# Agilent_3Ghz_option.net
KiCad netlist of a schematic drawn in Altium Designer
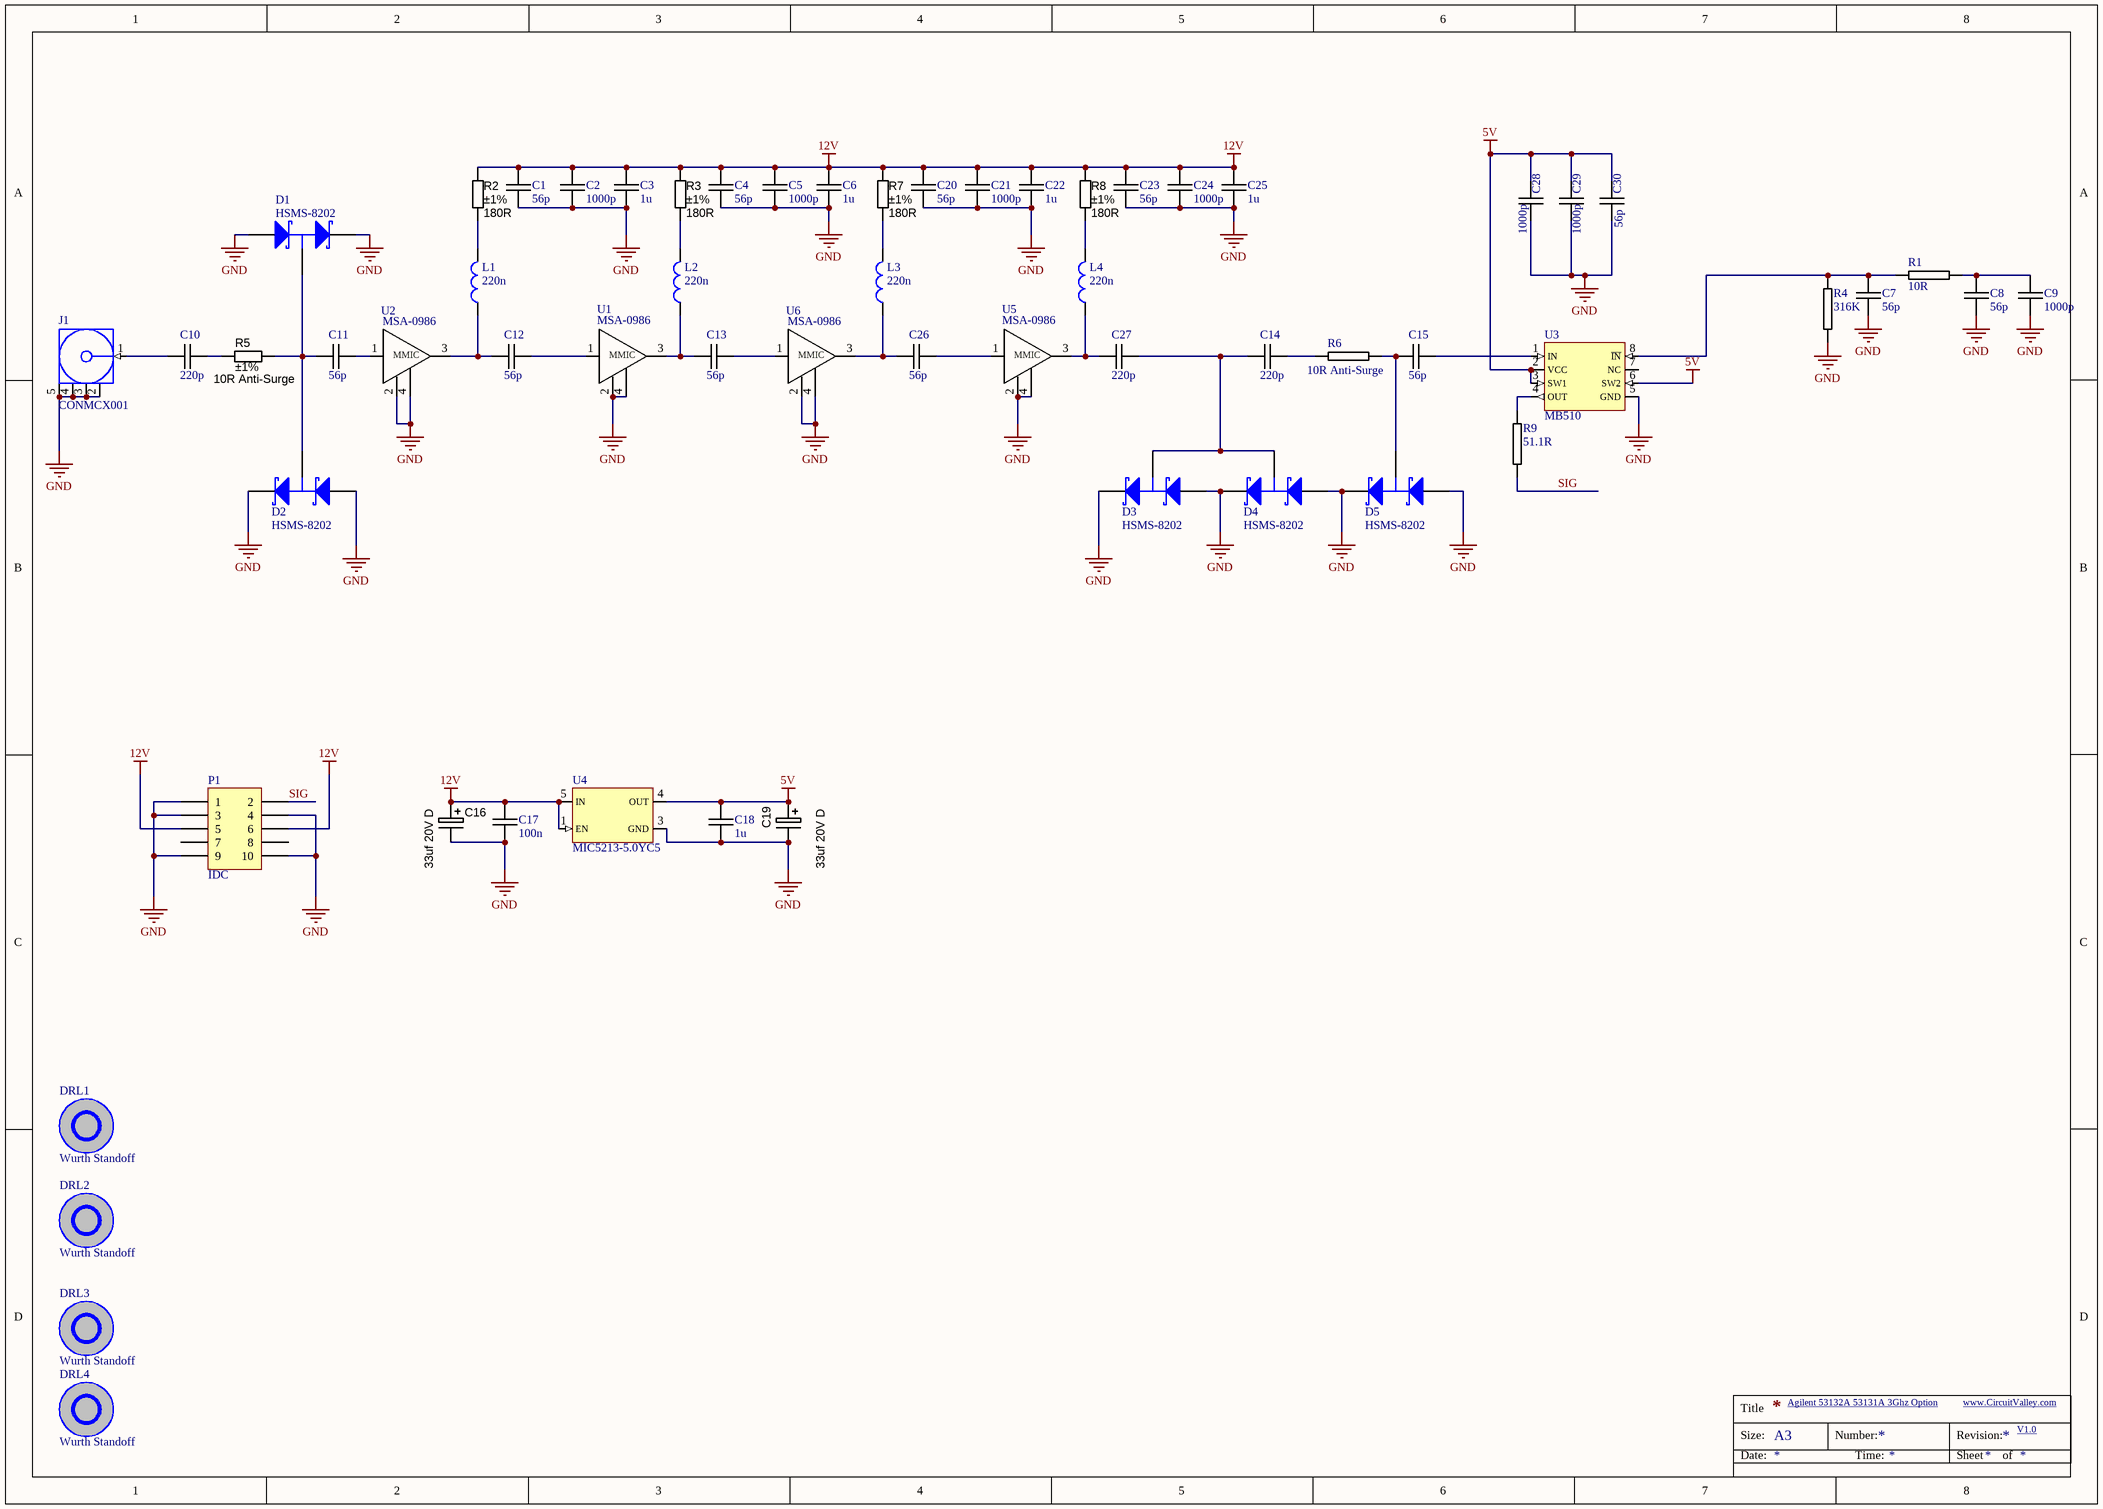
[diagram p0: Agilent_3Ghz_option.SchDoc]

(export (version "E")
  (design (tool "Eeschema 10.0.6"))
  (components
    (comp (ref "C1")
      (value "56p")
      (footprint "0805C-TBD")
      (description "CAPACITOR 0805 CERAMIC VALUE TO BE DETERMINED")
      (fields (field (name "PART") "CC0805FRNPO9BN560"))
      (libsource (lib "Generic") (part "0805C-TBD"))
    )
    (comp (ref "C2")
      (value "1000p")
      (footprint "0805C-TBD")
      (description "CAPACITOR 0805 CERAMIC VALUE TO BE DETERMINED")
      (fields (field (name "PART") "GRM2165C1H102FA01J"))
      (libsource (lib "Generic") (part "0805C-TBD"))
    )
    (comp (ref "C3")
      (value "1u")
      (footprint "0805C-TBD")
      (description "CAPACITOR 0805 CERAMIC VALUE TO BE DETERMINED")
      (fields (field (name "PART") "VJ0805V105ZXJCW1BC"))
      (libsource (lib "Generic") (part "0805C-TBD"))
    )
    (comp (ref "C4")
      (value "56p")
      (footprint "0805C-TBD")
      (description "CAPACITOR 0805 CERAMIC VALUE TO BE DETERMINED")
      (fields (field (name "PART") "CC0805FRNPO9BN560"))
      (libsource (lib "Generic") (part "0805C-TBD"))
    )
    (comp (ref "C5")
      (value "1000p")
      (footprint "0805C-TBD")
      (description "CAPACITOR 0805 CERAMIC VALUE TO BE DETERMINED")
      (fields (field (name "PART") "GRM2165C1H102FA01J"))
      (libsource (lib "Generic") (part "0805C-TBD"))
    )
    (comp (ref "C6")
      (value "1u")
      (footprint "0805C-TBD")
      (description "CAPACITOR 0805 CERAMIC VALUE TO BE DETERMINED")
      (fields (field (name "PART") "VJ0805V105ZXJCW1BC"))
      (libsource (lib "Generic") (part "0805C-TBD"))
    )
    (comp (ref "C7")
      (value "56p")
      (footprint "0805C-TBD")
      (description "CAPACITOR 0805 CERAMIC VALUE TO BE DETERMINED")
      (fields (field (name "PART") "CC0805FRNPO9BN560"))
      (libsource (lib "Generic") (part "0805C-TBD"))
    )
    (comp (ref "C8")
      (value "56p")
      (footprint "0805C-TBD")
      (description "CAPACITOR 0805 CERAMIC VALUE TO BE DETERMINED")
      (fields (field (name "PART") "CC0805FRNPO9BN560"))
      (libsource (lib "Generic") (part "0805C-TBD"))
    )
    (comp (ref "C9")
      (value "1000p")
      (footprint "0805C-TBD")
      (description "CAPACITOR 0805 CERAMIC VALUE TO BE DETERMINED")
      (fields (field (name "PART") "GRM2165C1H102FA01J"))
      (libsource (lib "Generic") (part "0805C-TBD"))
    )
    (comp (ref "C10")
      (value "220p")
      (footprint "0805C-TBD")
      (description "CAPACITOR 0805 CERAMIC VALUE TO BE DETERMINED")
      (fields (field (name "PART") "CC0805FRNPO9BN221"))
      (libsource (lib "Generic") (part "0805C-TBD"))
    )
    (comp (ref "C11")
      (value "56p")
      (footprint "0805C-TBD")
      (description "CAPACITOR 0805 CERAMIC VALUE TO BE DETERMINED")
      (fields (field (name "PART") "CC0805FRNPO9BN560"))
      (libsource (lib "Generic") (part "0805C-TBD"))
    )
    (comp (ref "C12")
      (value "56p")
      (footprint "0805C-TBD")
      (description "CAPACITOR 0805 CERAMIC VALUE TO BE DETERMINED")
      (fields (field (name "PART") "CC0805FRNPO9BN560"))
      (libsource (lib "Generic") (part "0805C-TBD"))
    )
    (comp (ref "C13")
      (value "56p")
      (footprint "0805C-TBD")
      (description "CAPACITOR 0805 CERAMIC VALUE TO BE DETERMINED")
      (fields (field (name "PART") "CC0805FRNPO9BN560"))
      (libsource (lib "Generic") (part "0805C-TBD"))
    )
    (comp (ref "C14")
      (value "220p")
      (footprint "0805C-TBD")
      (description "CAPACITOR 0805 CERAMIC VALUE TO BE DETERMINED")
      (fields (field (name "PART") "CC0805FRNPO9BN221"))
      (libsource (lib "Generic") (part "0805C-TBD"))
    )
    (comp (ref "C15")
      (value "56p")
      (footprint "0805C-TBD")
      (description "CAPACITOR 0805 CERAMIC VALUE TO BE DETERMINED")
      (fields (field (name "PART") "CC0805FRNPO9BN560"))
      (libsource (lib "Generic") (part "0805C-TBD"))
    )
    (comp (ref "C16")
      (value "33uf 20V D")
      (footprint "CAPMP7343X310N")
      (description "Capacitor SMD Tant 330uF 20% 6V3 2917")
      (fields
        (field (name "TOLERANCE") "±20%")
        (field (name "MANUFACTURER PART NUMBER") "T520D337M006ATE015")
      )
      (libsource (lib "PBL - Capacitors") (part "CAPT_330u_2917_6V3"))
    )
    (comp (ref "C17")
      (value "100n")
      (footprint "0805C-TBD")
      (description "CAPACITOR 0805 CERAMIC VALUE TO BE DETERMINED")
      (fields (field (name "PART") "GRM21BR71H104KA01K"))
      (libsource (lib "Generic") (part "0805C-TBD"))
    )
    (comp (ref "C18")
      (value "1u")
      (footprint "0805C-TBD")
      (description "CAPACITOR 0805 CERAMIC VALUE TO BE DETERMINED")
      (fields (field (name "PART") "VJ0805V105ZXJCW1BC"))
      (libsource (lib "Generic") (part "0805C-TBD"))
    )
    (comp (ref "C19")
      (value "33uf 20V D")
      (footprint "CAPMP7343X310N")
      (description "Capacitor SMD Tant 330uF 20% 6V3 2917")
      (fields
        (field (name "TOLERANCE") "±20%")
        (field (name "MANUFACTURER PART NUMBER") "T520D337M006ATE015")
      )
      (libsource (lib "PBL - Capacitors") (part "CAPT_330u_2917_6V3"))
    )
    (comp (ref "C20")
      (value "56p")
      (footprint "0805C-TBD")
      (description "CAPACITOR 0805 CERAMIC VALUE TO BE DETERMINED")
      (fields (field (name "PART") "CC0805FRNPO9BN560"))
      (libsource (lib "Generic") (part "0805C-TBD"))
    )
    (comp (ref "C21")
      (value "1000p")
      (footprint "0805C-TBD")
      (description "CAPACITOR 0805 CERAMIC VALUE TO BE DETERMINED")
      (fields (field (name "PART") "GRM2165C1H102FA01J"))
      (libsource (lib "Generic") (part "0805C-TBD"))
    )
    (comp (ref "C22")
      (value "1u")
      (footprint "0805C-TBD")
      (description "CAPACITOR 0805 CERAMIC VALUE TO BE DETERMINED")
      (fields (field (name "PART") "VJ0805V105ZXJCW1BC"))
      (libsource (lib "Generic") (part "0805C-TBD"))
    )
    (comp (ref "C23")
      (value "56p")
      (footprint "0805C-TBD")
      (description "CAPACITOR 0805 CERAMIC VALUE TO BE DETERMINED")
      (fields (field (name "PART") "CC0805FRNPO9BN560"))
      (libsource (lib "Generic") (part "0805C-TBD"))
    )
    (comp (ref "C24")
      (value "1000p")
      (footprint "0805C-TBD")
      (description "CAPACITOR 0805 CERAMIC VALUE TO BE DETERMINED")
      (fields (field (name "PART") "GRM2165C1H102FA01J"))
      (libsource (lib "Generic") (part "0805C-TBD"))
    )
    (comp (ref "C25")
      (value "1u")
      (footprint "0805C-TBD")
      (description "CAPACITOR 0805 CERAMIC VALUE TO BE DETERMINED")
      (fields (field (name "PART") "VJ0805V105ZXJCW1BC"))
      (libsource (lib "Generic") (part "0805C-TBD"))
    )
    (comp (ref "C26")
      (value "56p")
      (footprint "0805C-TBD")
      (description "CAPACITOR 0805 CERAMIC VALUE TO BE DETERMINED")
      (fields (field (name "PART") "CC0805FRNPO9BN560"))
      (libsource (lib "Generic") (part "0805C-TBD"))
    )
    (comp (ref "C27")
      (value "220p")
      (footprint "0805C-TBD")
      (description "CAPACITOR 0805 CERAMIC VALUE TO BE DETERMINED")
      (fields (field (name "PART") "CC0805FRNPO9BN221"))
      (libsource (lib "Generic") (part "0805C-TBD"))
    )
    (comp (ref "C28")
      (value "1000p")
      (footprint "0805C-TBD")
      (description "CAPACITOR 0805 CERAMIC VALUE TO BE DETERMINED")
      (fields (field (name "PART") "GRM2165C1H102FA01J"))
      (libsource (lib "Generic") (part "0805C-TBD"))
    )
    (comp (ref "C29")
      (value "1000p")
      (footprint "0805C-TBD")
      (description "CAPACITOR 0805 CERAMIC VALUE TO BE DETERMINED")
      (fields (field (name "PART") "GRM2165C1H102FA01J"))
      (libsource (lib "Generic") (part "0805C-TBD"))
    )
    (comp (ref "C30")
      (value "56p")
      (footprint "0805C-TBD")
      (description "CAPACITOR 0805 CERAMIC VALUE TO BE DETERMINED")
      (fields (field (name "PART") "CC0805FRNPO9BN560"))
      (libsource (lib "Generic") (part "0805C-TBD"))
    )
    (comp (ref "D1")
      (value "HSMS-8202")
      (footprint "SOT23_N")
      (description "Schottky Barrier Double Diode")
      (fields (field (name "PUBLISHER") "Altium Limited"))
      (libsource (lib "Philips Discrete Diode - Schottky") (part "BAT54S"))
    )
    (comp (ref "D2")
      (value "HSMS-8202")
      (footprint "SOT23_N")
      (description "Schottky Barrier Double Diode")
      (fields (field (name "PUBLISHER") "Altium Limited"))
      (libsource (lib "Philips Discrete Diode - Schottky") (part "BAT54S"))
    )
    (comp (ref "D3")
      (value "HSMS-8202")
      (footprint "SOT23_N")
      (description "Schottky Barrier Double Diode")
      (fields (field (name "PUBLISHER") "Altium Limited"))
      (libsource (lib "Philips Discrete Diode - Schottky") (part "BAT54S"))
    )
    (comp (ref "D4")
      (value "HSMS-8202")
      (footprint "SOT23_N")
      (description "Schottky Barrier Double Diode")
      (fields (field (name "PUBLISHER") "Altium Limited"))
      (libsource (lib "Philips Discrete Diode - Schottky") (part "BAT54S"))
    )
    (comp (ref "D5")
      (value "HSMS-8202")
      (footprint "SOT23_N")
      (description "Schottky Barrier Double Diode")
      (fields (field (name "PUBLISHER") "Altium Limited"))
      (libsource (lib "Philips Discrete Diode - Schottky") (part "BAT54S"))
    )
    (comp (ref "DRL1")
      (value "Wurth Standoff")
      (footprint "Wurth_PCB_STANDOFF_7740_6mm")
      (fields (field (name "PART") "9774080360"))
      (libsource (lib "cvlib") (part "PCB_Sandoff"))
    )
    (comp (ref "DRL2")
      (value "Wurth Standoff")
      (footprint "Wurth_PCB_STANDOFF_7740_6mm")
      (fields (field (name "PART") "9774080360"))
      (libsource (lib "cvlib") (part "PCB_Sandoff"))
    )
    (comp (ref "DRL3")
      (value "Wurth Standoff")
      (footprint "Wurth_PCB_STANDOFF_7740_6mm")
      (fields (field (name "PART") "9774080360"))
      (libsource (lib "cvlib") (part "PCB_Sandoff"))
    )
    (comp (ref "DRL4")
      (value "Wurth Standoff")
      (footprint "Wurth_PCB_STANDOFF_7740_6mm")
      (fields (field (name "PART") "9774080360"))
      (libsource (lib "cvlib") (part "PCB_Sandoff"))
    )
    (comp (ref "J1")
      (value "CONMCX001")
      (footprint "CON-MCX")
      (description "MCX Female PCB Mount Connector, Thru-Hole")
      (fields (field (name "PART") "919-382J-51P"))
      (libsource (lib "Linx Technologies Connector") (part "CONMCX001"))
    )
    (comp (ref "L1")
      (value "220n")
      (footprint "NLV32T")
      (fields (field (name "PARTNUMBER") "NLV32T-R22J-EF"))
      (libsource (lib "Inductor") (part "inductor_smd"))
    )
    (comp (ref "L2")
      (value "220n")
      (footprint "NLV32T")
      (fields (field (name "PARTNUMBER") "NLV32T-R22J-EF"))
      (libsource (lib "Inductor") (part "inductor_smd"))
    )
    (comp (ref "L3")
      (value "220n")
      (footprint "NLV32T")
      (fields (field (name "PARTNUMBER") "NLV32T-R22J-EF"))
      (libsource (lib "Inductor") (part "inductor_smd"))
    )
    (comp (ref "L4")
      (value "220n")
      (footprint "NLV32T")
      (fields (field (name "PARTNUMBER") "NLV32T-R22J-EF"))
      (libsource (lib "Inductor") (part "inductor_smd"))
    )
    (comp (ref "P1")
      (value "IDC")
      (footprint "HDR2X5")
      (description "Header, 5-Pin, Dual row")
      (fields (field (name "PART") "69830010LF") (field (name "PUBLISHER") "Altium Limited"))
      (libsource (lib "Miscellaneous Connectors") (part "Header 5X2"))
    )
    (comp (ref "R1")
      (value "10R")
      (footprint "0805R-TBD")
      (description "RESISTOR 0805 VALUE TO BE DETERMINED")
      (fields (field (name "PART") "ESR10EZPJ100"))
      (libsource (lib "Generic") (part "0805R-TBD"))
    )
    (comp (ref "R2")
      (value "180R")
      (footprint "RESC5025N")
      (description "Resistor SMD chip 1 Ohm 1W 1% 2010")
      (fields
        (field (name "TOLERANCE") "±1%")
        (field (name "PART") "RC2010FK-07180RL")
        (field (name "Comment") "Thick Film")
      )
      (libsource (lib "PBL - Resistors") (part "RES_1R_2010_1%"))
    )
    (comp (ref "R3")
      (value "180R")
      (footprint "RESC5025N")
      (description "Resistor SMD chip 1 Ohm 1W 1% 2010")
      (fields
        (field (name "TOLERANCE") "±1%")
        (field (name "PART") "RC2010FK-07180RL")
        (field (name "Comment") "Thick Film")
      )
      (libsource (lib "PBL - Resistors") (part "RES_1R_2010_1%"))
    )
    (comp (ref "R4")
      (value "316K")
      (footprint "0805R-TBD")
      (description "RESISTOR 0805 VALUE TO BE DETERMINED")
      (fields (field (name "PART") "RK73H2ATTD3163F"))
      (libsource (lib "Generic") (part "0805R-TBD"))
    )
    (comp (ref "R5")
      (value "10R Anti-Surge")
      (footprint "RESC5025N")
      (description "Resistor SMD chip 1 Ohm 1W 1% 2010")
      (fields
        (field (name "TOLERANCE") "±1%")
        (field (name "PART") "CRS2010-FX-10R0ELF")
        (field (name "Comment") "Thick Film")
      )
      (libsource (lib "") (part "RES_1R_2010_1%_1"))
    )
    (comp (ref "R6")
      (value "10R Anti-Surge")
      (footprint "0805R-TBD")
      (description "RESISTOR 0805 VALUE TO BE DETERMINED")
      (fields (field (name "PART") "ESR10EZPJ100"))
      (libsource (lib "Generic") (part "0805R-TBD"))
    )
    (comp (ref "R7")
      (value "180R")
      (footprint "RESC5025N")
      (description "Resistor SMD chip 1 Ohm 1W 1% 2010")
      (fields
        (field (name "TOLERANCE") "±1%")
        (field (name "PART") "RC2010FK-07180RL")
        (field (name "Comment") "Thick Film")
      )
      (libsource (lib "PBL - Resistors") (part "RES_1R_2010_1%"))
    )
    (comp (ref "R8")
      (value "180R")
      (footprint "RESC5025N")
      (description "Resistor SMD chip 1 Ohm 1W 1% 2010")
      (fields
        (field (name "TOLERANCE") "±1%")
        (field (name "PART") "RC2010FK-07180RL")
        (field (name "Comment") "Thick Film")
      )
      (libsource (lib "PBL - Resistors") (part "RES_1R_2010_1%"))
    )
    (comp (ref "R9")
      (value "51.1R")
      (footprint "0805R-TBD")
      (description "RESISTOR 0805 VALUE TO BE DETERMINED")
      (fields (field (name "PART") "RK73H2ATTE51R1F"))
      (libsource (lib "Generic") (part "0805R-TBD"))
    )
    (comp (ref "U1")
      (value "MSA-0986")
      (footprint "SOT-86")
      (libsource (lib "cvlib") (part "MMIC_SOT86_AG302-86G_SGA-5386Z"))
    )
    (comp (ref "U2")
      (value "MSA-0986")
      (footprint "SOT-86")
      (libsource (lib "cvlib") (part "MMIC_SOT86_AG302-86G_SGA-5386Z"))
    )
    (comp (ref "U3") (value "MB510") (footprint "FPT-08P-M01") (libsource (lib "cvlib") (part "MB510")))
    (comp (ref "U4") (value "MIC5213-5.0YC5") (footprint "SC70-5") (libsource (lib "cvlib") (part "MIC5213")))
    (comp (ref "U5")
      (value "MSA-0986")
      (footprint "SOT-86")
      (libsource (lib "cvlib") (part "MMIC_SOT86_AG302-86G_SGA-5386Z"))
    )
    (comp (ref "U6")
      (value "MSA-0986")
      (footprint "SOT-86")
      (libsource (lib "cvlib") (part "MMIC_SOT86_AG302-86G_SGA-5386Z"))
    )
  )
  (nets
    (net (code "1") (name "/SIG") (class "Default")
      (node (ref "P1") (pin "2") (pinfunction "2_2") (pintype "passive"))
      (node (ref "R9") (pin "2") (pintype "passive"))
    )
    (net (code "2") (name "5V") (class "Default")
      (node (ref "C18") (pin "2") (pintype "passive"))
      (node (ref "C19") (pin "1") (pintype "passive"))
      (node (ref "C28") (pin "1") (pintype "passive"))
      (node (ref "C29") (pin "1") (pintype "passive"))
      (node (ref "C30") (pin "2") (pintype "passive"))
      (node (ref "U3") (pin "2") (pinfunction "VCC_2") (pintype "power_in"))
      (node (ref "U3") (pin "3") (pinfunction "SW1_3") (pintype "input"))
      (node (ref "U3") (pin "6") (pinfunction "SW2_6") (pintype "input"))
      (node (ref "U4") (pin "4") (pinfunction "OUT_4") (pintype "power_in"))
    )
    (net (code "3") (name "12V") (class "Default")
      (node (ref "C1") (pin "2") (pintype "passive"))
      (node (ref "C16") (pin "1") (pintype "passive"))
      (node (ref "C17") (pin "2") (pintype "passive"))
      (node (ref "C2") (pin "2") (pintype "passive"))
      (node (ref "C20") (pin "2") (pintype "passive"))
      (node (ref "C21") (pin "2") (pintype "passive"))
      (node (ref "C22") (pin "2") (pintype "passive"))
      (node (ref "C23") (pin "2") (pintype "passive"))
      (node (ref "C24") (pin "2") (pintype "passive"))
      (node (ref "C25") (pin "2") (pintype "passive"))
      (node (ref "C3") (pin "2") (pintype "passive"))
      (node (ref "C4") (pin "2") (pintype "passive"))
      (node (ref "C5") (pin "2") (pintype "passive"))
      (node (ref "C6") (pin "2") (pintype "passive"))
      (node (ref "P1") (pin "5") (pinfunction "5_5") (pintype "passive"))
      (node (ref "P1") (pin "6") (pinfunction "6_6") (pintype "passive"))
      (node (ref "R2") (pin "1") (pinfunction "1_1") (pintype "passive"))
      (node (ref "R3") (pin "1") (pinfunction "1_1") (pintype "passive"))
      (node (ref "R7") (pin "1") (pinfunction "1_1") (pintype "passive"))
      (node (ref "R8") (pin "1") (pinfunction "1_1") (pintype "passive"))
      (node (ref "U4") (pin "1") (pinfunction "EN_1") (pintype "input"))
      (node (ref "U4") (pin "5") (pinfunction "IN_5") (pintype "power_in"))
    )
    (net (code "4") (name "GND") (class "Default")
      (node (ref "C1") (pin "1") (pintype "passive"))
      (node (ref "C16") (pin "2") (pintype "passive"))
      (node (ref "C17") (pin "1") (pintype "passive"))
      (node (ref "C18") (pin "1") (pintype "passive"))
      (node (ref "C19") (pin "2") (pintype "passive"))
      (node (ref "C2") (pin "1") (pintype "passive"))
      (node (ref "C20") (pin "1") (pintype "passive"))
      (node (ref "C21") (pin "1") (pintype "passive"))
      (node (ref "C22") (pin "1") (pintype "passive"))
      (node (ref "C23") (pin "1") (pintype "passive"))
      (node (ref "C24") (pin "1") (pintype "passive"))
      (node (ref "C25") (pin "1") (pintype "passive"))
      (node (ref "C28") (pin "2") (pintype "passive"))
      (node (ref "C29") (pin "2") (pintype "passive"))
      (node (ref "C3") (pin "1") (pintype "passive"))
      (node (ref "C30") (pin "1") (pintype "passive"))
      (node (ref "C4") (pin "1") (pintype "passive"))
      (node (ref "C5") (pin "1") (pintype "passive"))
      (node (ref "C6") (pin "1") (pintype "passive"))
      (node (ref "C7") (pin "1") (pintype "passive"))
      (node (ref "C8") (pin "1") (pintype "passive"))
      (node (ref "C9") (pin "1") (pintype "passive"))
      (node (ref "D1") (pin "1") (pinfunction "A_1") (pintype "passive"))
      (node (ref "D1") (pin "2") (pinfunction "K_2") (pintype "passive"))
      (node (ref "D2") (pin "1") (pinfunction "A_1") (pintype "passive"))
      (node (ref "D2") (pin "2") (pinfunction "K_2") (pintype "passive"))
      (node (ref "D3") (pin "1") (pinfunction "A_1") (pintype "passive"))
      (node (ref "D3") (pin "2") (pinfunction "K_2") (pintype "passive"))
      (node (ref "D4") (pin "1") (pinfunction "A_1") (pintype "passive"))
      (node (ref "D4") (pin "2") (pinfunction "K_2") (pintype "passive"))
      (node (ref "D5") (pin "1") (pinfunction "A_1") (pintype "passive"))
      (node (ref "D5") (pin "2") (pinfunction "K_2") (pintype "passive"))
      (node (ref "J1") (pin "2") (pinfunction "GND_2") (pintype "power_in"))
      (node (ref "J1") (pin "3") (pinfunction "GND_3") (pintype "power_in"))
      (node (ref "J1") (pin "4") (pinfunction "GND_4") (pintype "power_in"))
      (node (ref "J1") (pin "5") (pinfunction "GND_5") (pintype "power_in"))
      (node (ref "P1") (pin "1") (pinfunction "1_1") (pintype "passive"))
      (node (ref "P1") (pin "10") (pinfunction "10_10") (pintype "passive"))
      (node (ref "P1") (pin "3") (pinfunction "3_3") (pintype "passive"))
      (node (ref "P1") (pin "4") (pinfunction "4_4") (pintype "passive"))
      (node (ref "P1") (pin "9") (pinfunction "9_9") (pintype "passive"))
      (node (ref "R4") (pin "1") (pintype "passive"))
      (node (ref "U1") (pin "2") (pinfunction "2_2") (pintype "power_in"))
      (node (ref "U1") (pin "4") (pinfunction "4_4") (pintype "power_in"))
      (node (ref "U2") (pin "2") (pinfunction "2_2") (pintype "power_in"))
      (node (ref "U2") (pin "4") (pinfunction "4_4") (pintype "power_in"))
      (node (ref "U3") (pin "5") (pinfunction "GND_5") (pintype "power_in"))
      (node (ref "U4") (pin "3") (pinfunction "GND_3") (pintype "passive"))
      (node (ref "U5") (pin "2") (pinfunction "2_2") (pintype "power_in"))
      (node (ref "U5") (pin "4") (pinfunction "4_4") (pintype "power_in"))
      (node (ref "U6") (pin "2") (pinfunction "2_2") (pintype "power_in"))
      (node (ref "U6") (pin "4") (pinfunction "4_4") (pintype "power_in"))
    )
    (net (code "5") (name "Net-(C8-Pad2)") (class "Default")
      (node (ref "C8") (pin "2") (pintype "passive"))
      (node (ref "C9") (pin "2") (pintype "passive"))
      (node (ref "R1") (pin "2") (pintype "passive"))
    )
    (net (code "6") (name "Net-(C10-Pad2)") (class "Default")
      (node (ref "C10") (pin "2") (pintype "passive"))
      (node (ref "R5") (pin "1") (pinfunction "1_1") (pintype "passive"))
    )
    (net (code "7") (name "Net-(C12-Pad1)") (class "Default")
      (node (ref "C12") (pin "1") (pintype "passive"))
      (node (ref "L1") (pin "1") (pinfunction "1_1") (pintype "passive"))
      (node (ref "U2") (pin "3") (pinfunction "3_3") (pintype "power_in"))
    )
    (net (code "8") (name "Net-(C13-Pad1)") (class "Default")
      (node (ref "C13") (pin "1") (pintype "passive"))
      (node (ref "L2") (pin "1") (pinfunction "1_1") (pintype "passive"))
      (node (ref "U1") (pin "3") (pinfunction "3_3") (pintype "power_in"))
    )
    (net (code "9") (name "Net-(C14-Pad2)") (class "Default")
      (node (ref "C14") (pin "2") (pintype "passive"))
      (node (ref "R6") (pin "1") (pintype "passive"))
    )
    (net (code "10") (name "Net-(C26-Pad1)") (class "Default")
      (node (ref "C26") (pin "1") (pintype "passive"))
      (node (ref "L3") (pin "1") (pinfunction "1_1") (pintype "passive"))
      (node (ref "U6") (pin "3") (pinfunction "3_3") (pintype "power_in"))
    )
    (net (code "11") (name "Net-(C27-Pad1)") (class "Default")
      (node (ref "C27") (pin "1") (pintype "passive"))
      (node (ref "L4") (pin "1") (pinfunction "1_1") (pintype "passive"))
      (node (ref "U5") (pin "3") (pinfunction "3_3") (pintype "power_in"))
    )
    (net (code "12") (name "Net-(D1-C)") (class "Default")
      (node (ref "C11") (pin "1") (pintype "passive"))
      (node (ref "D1") (pin "3") (pinfunction "C_3") (pintype "passive"))
      (node (ref "D2") (pin "3") (pinfunction "C_3") (pintype "passive"))
      (node (ref "R5") (pin "2") (pinfunction "2_2") (pintype "passive"))
    )
    (net (code "13") (name "Net-(D3-C)") (class "Default")
      (node (ref "C14") (pin "1") (pintype "passive"))
      (node (ref "C27") (pin "2") (pintype "passive"))
      (node (ref "D3") (pin "3") (pinfunction "C_3") (pintype "passive"))
      (node (ref "D4") (pin "3") (pinfunction "C_3") (pintype "passive"))
    )
    (net (code "14") (name "Net-(D5-C)") (class "Default")
      (node (ref "C15") (pin "1") (pintype "passive"))
      (node (ref "D5") (pin "3") (pinfunction "C_3") (pintype "passive"))
      (node (ref "R6") (pin "2") (pintype "passive"))
    )
    (net (code "15") (name "Net-(J1-Signal)") (class "Default")
      (node (ref "C10") (pin "1") (pintype "passive"))
      (node (ref "J1") (pin "1") (pinfunction "Signal_1") (pintype "input"))
    )
    (net (code "16") (name "Net-(L1-Pad2)") (class "Default")
      (node (ref "L1") (pin "2") (pinfunction "2_2") (pintype "passive"))
      (node (ref "R2") (pin "2") (pinfunction "2_2") (pintype "passive"))
    )
    (net (code "17") (name "Net-(L2-Pad2)") (class "Default")
      (node (ref "L2") (pin "2") (pinfunction "2_2") (pintype "passive"))
      (node (ref "R3") (pin "2") (pinfunction "2_2") (pintype "passive"))
    )
    (net (code "18") (name "Net-(L3-Pad2)") (class "Default")
      (node (ref "L3") (pin "2") (pinfunction "2_2") (pintype "passive"))
      (node (ref "R7") (pin "2") (pinfunction "2_2") (pintype "passive"))
    )
    (net (code "19") (name "Net-(L4-Pad2)") (class "Default")
      (node (ref "L4") (pin "2") (pinfunction "2_2") (pintype "passive"))
      (node (ref "R8") (pin "2") (pinfunction "2_2") (pintype "passive"))
    )
    (net (code "20") (name "Net-(U1-IN)") (class "Default")
      (node (ref "C12") (pin "2") (pintype "passive"))
      (node (ref "U1") (pin "1") (pinfunction "IN_1") (pintype "power_in"))
    )
    (net (code "21") (name "Net-(U2-IN)") (class "Default")
      (node (ref "C11") (pin "2") (pintype "passive"))
      (node (ref "U2") (pin "1") (pinfunction "IN_1") (pintype "power_in"))
    )
    (net (code "22") (name "Net-(U3-IN)") (class "Default")
      (node (ref "C15") (pin "2") (pintype "passive"))
      (node (ref "U3") (pin "1") (pinfunction "IN_1") (pintype "input"))
    )
    (net (code "23") (name "Net-(U3-OUT)") (class "Default")
      (node (ref "R9") (pin "1") (pintype "passive"))
      (node (ref "U3") (pin "4") (pinfunction "OUT_4") (pintype "output"))
    )
    (net (code "24") (name "Net-(U3-~{IN})") (class "Default")
      (node (ref "C7") (pin "2") (pintype "passive"))
      (node (ref "R1") (pin "1") (pintype "passive"))
      (node (ref "R4") (pin "2") (pintype "passive"))
      (node (ref "U3") (pin "8") (pinfunction "~{IN}_8") (pintype "input"))
    )
    (net (code "25") (name "Net-(U5-IN)") (class "Default")
      (node (ref "C26") (pin "2") (pintype "passive"))
      (node (ref "U5") (pin "1") (pinfunction "IN_1") (pintype "power_in"))
    )
    (net (code "26") (name "Net-(U6-IN)") (class "Default")
      (node (ref "C13") (pin "2") (pintype "passive"))
      (node (ref "U6") (pin "1") (pinfunction "IN_1") (pintype "power_in"))
    )
    (net (code "27") (name "unconnected-(P1-Pad7)") (class "Default")
      (node (ref "P1") (pin "7") (pinfunction "7_7") (pintype "passive"))
    )
    (net (code "28") (name "unconnected-(P1-Pad8)") (class "Default")
      (node (ref "P1") (pin "8") (pinfunction "8_8") (pintype "passive"))
    )
    (net (code "29") (name "unconnected-(U3-NC-Pad7)") (class "Default")
      (node (ref "U3") (pin "7") (pinfunction "NC_7") (pintype "passive"))
    )
  )
)
